# 2_ESP32.net
KiCad netlist of a schematic drawn in Altium Designer
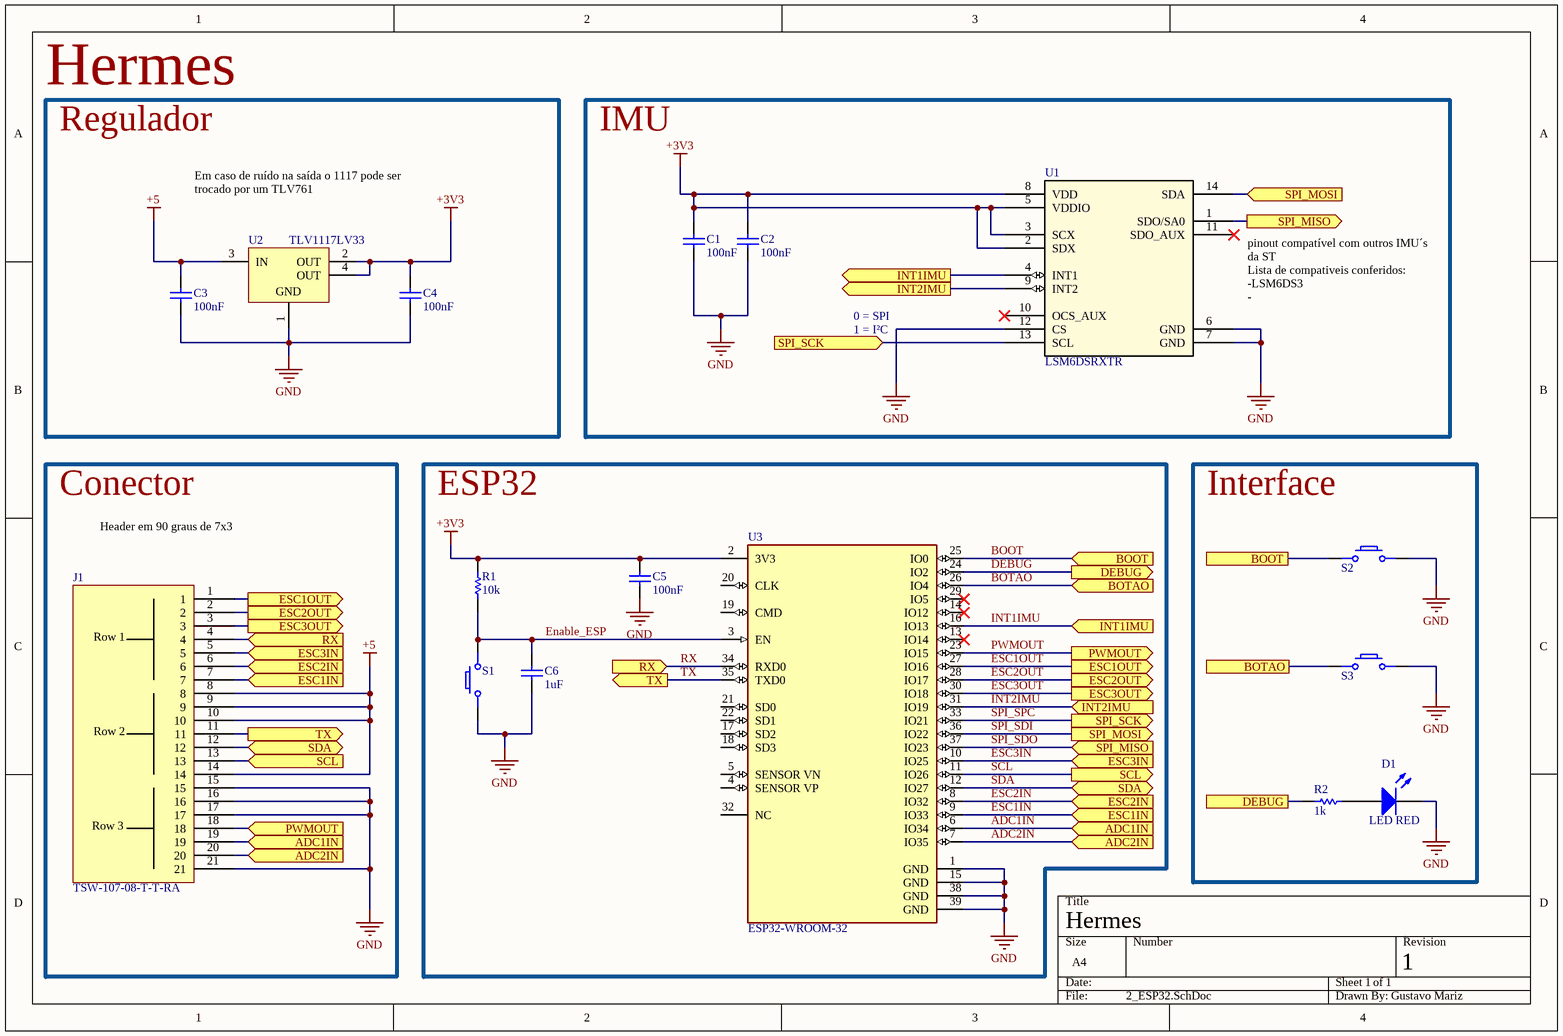
[diagram p0: 2_ESP32.SchDoc]

(export (version "E")
  (design (tool "Eeschema 10.0.6"))
  (components
    (comp (ref "C1")
      (value "CAP")
      (footprint "0603")
      (description "Capacitor")
      (fields (field (name "VALOR") "100nF"))
      (libsource (lib "Biblioteca Trincabotz (1)") (part "CAP. CERÂMICO"))
    )
    (comp (ref "C2")
      (value "CAP")
      (footprint "0603")
      (description "Capacitor")
      (fields (field (name "VALOR") "100nF"))
      (libsource (lib "Biblioteca Trincabotz (1)") (part "CAP. CERÂMICO"))
    )
    (comp (ref "C3")
      (value "CAP")
      (footprint "0603")
      (description "Capacitor")
      (fields (field (name "VALOR") "100nF"))
      (libsource (lib "Biblioteca Trincabotz (1)") (part "CAP. CERÂMICO"))
    )
    (comp (ref "C4")
      (value "CAP")
      (footprint "0603")
      (description "Capacitor")
      (fields (field (name "VALOR") "100nF"))
      (libsource (lib "Biblioteca Trincabotz (1)") (part "CAP. CERÂMICO"))
    )
    (comp (ref "C5")
      (value "CAP")
      (footprint "0603")
      (description "Capacitor")
      (fields (field (name "VALOR") "100nF"))
      (libsource (lib "Biblioteca Trincabotz (1)") (part "CAP. CERÂMICO"))
    )
    (comp (ref "C6")
      (value "CAP")
      (footprint "0603")
      (description "Capacitor")
      (fields (field (name "VALOR") "1uF"))
      (libsource (lib "Biblioteca Trincabotz (1)") (part "CAP. CERÂMICO"))
    )
    (comp (ref "D1")
      (value "LED RED")
      (footprint "LED 0805")
      (libsource (lib "Biblioteca Trincabotz (1)") (part "LED"))
    )
    (comp (ref "J1")
      (value "TSW-107-08-T-T-RA")
      (footprint "TSW-107-08-T-T-RA_SAI")
      (description "No Description Available")
      (libsource (lib "3x7pinheader") (part "TSW-107-08-T-T-RA"))
    )
    (comp (ref "R1")
      (value "10k")
      (footprint "RES 0603")
      (description "Resistor")
      (fields (field (name "Comment") "RESISTOR"))
      (libsource (lib "Biblioteca Trincabotz (1)") (part "RESISTOR"))
    )
    (comp (ref "R2")
      (value "1k")
      (footprint "RES 0603")
      (description "Resistor")
      (fields (field (name "Comment") "RESISTOR"))
      (libsource (lib "Biblioteca Trincabotz (1)") (part "RESISTOR"))
    )
    (comp (ref "S1")
      (value "PushButtonSMD")
      (footprint "PUSHBUTTON.SMD")
      (libsource (lib "Biblioteca Trincabotz (1)") (part "PushButtonSMD"))
    )
    (comp (ref "S2")
      (value "PushButtonSMD")
      (footprint "PUSHBUTTON.SMD")
      (libsource (lib "Biblioteca Trincabotz (1)") (part "PushButtonSMD"))
    )
    (comp (ref "S3")
      (value "PushButtonSMD")
      (footprint "PUSHBUTTON.SMD")
      (libsource (lib "Biblioteca Trincabotz (1)") (part "PushButtonSMD"))
    )
    (comp (ref "U1")
      (value "LSM6DSRXTR")
      (footprint "LGA-14L_STM")
      (description "No Description Available")
      (libsource (lib "LSM6DSRXTR") (part "LSM6DSRXTR"))
    )
    (comp (ref "U2")
      (value "TLV1117LV33")
      (footprint "DCY0004A_N")
      (fields (field (name "MANUFACTURER") "Texas Instruments") (field (name "PARTNUMBER") "TLV1117LV33DCYR"))
      (libsource (lib "Altium Content Vault") (part "TI-TLV1117LV33DCY4"))
    )
    (comp (ref "U3")
      (value "ESP32-WROOM-32")
      (footprint "FP-ESP32-WROOM-32-MFG")
      (description "RX TXRX MOD WIFI SURFACE MOUNT")
      (libsource (lib "Altium Content Vault") (part "ee866abf0b6c51247b7f5cdebf2f250"))
    )
  )
  (nets
    (net (code "1") (name "+3V3") (class "Default")
      (node (ref "C1") (pin "2") (pinfunction "2_2") (pintype "passive"))
      (node (ref "C2") (pin "2") (pinfunction "2_2") (pintype "passive"))
      (node (ref "C4") (pin "2") (pinfunction "2_2") (pintype "passive"))
      (node (ref "C5") (pin "2") (pinfunction "2_2") (pintype "passive"))
      (node (ref "R1") (pin "2") (pinfunction "2_2") (pintype "passive"))
      (node (ref "U1") (pin "2") (pinfunction "SDX_2") (pintype "passive"))
      (node (ref "U1") (pin "3") (pinfunction "SCX_3") (pintype "passive"))
      (node (ref "U1") (pin "5") (pinfunction "VDDIO_5") (pintype "power_in"))
      (node (ref "U1") (pin "8") (pinfunction "VDD_8") (pintype "power_in"))
      (node (ref "U2") (pin "2") (pinfunction "OUT_2") (pintype "power_in"))
      (node (ref "U2") (pin "4") (pinfunction "OUT_4") (pintype "power_in"))
      (node (ref "U3") (pin "2") (pinfunction "3V3_2") (pintype "power_in"))
    )
    (net (code "2") (name "+5") (class "Default")
      (node (ref "C3") (pin "2") (pinfunction "2_2") (pintype "passive"))
      (node (ref "J1") (pin "10") (pinfunction "10_10") (pintype "passive"))
      (node (ref "J1") (pin "14") (pinfunction "14_14") (pintype "passive"))
      (node (ref "J1") (pin "8") (pinfunction "8_8") (pintype "passive"))
      (node (ref "J1") (pin "9") (pinfunction "9_9") (pintype "passive"))
      (node (ref "U2") (pin "3") (pinfunction "IN_3") (pintype "power_in"))
    )
    (net (code "3") (name "/ADC1IN") (class "Default")
      (node (ref "J1") (pin "19") (pinfunction "19_19") (pintype "passive"))
      (node (ref "U3") (pin "6") (pinfunction "IO34_6") (pintype "bidirectional"))
    )
    (net (code "4") (name "/ADC2IN") (class "Default")
      (node (ref "J1") (pin "20") (pinfunction "20_20") (pintype "passive"))
      (node (ref "U3") (pin "7") (pinfunction "IO35_7") (pintype "bidirectional"))
    )
    (net (code "5") (name "/BOOT") (class "Default")
      (node (ref "S2") (pin "1") (pinfunction "1_1") (pintype "passive"))
      (node (ref "U3") (pin "25") (pinfunction "IO0_25") (pintype "bidirectional"))
    )
    (net (code "6") (name "/BOTAO") (class "Default")
      (node (ref "S3") (pin "1") (pinfunction "1_1") (pintype "passive"))
      (node (ref "U3") (pin "26") (pinfunction "IO4_26") (pintype "bidirectional"))
    )
    (net (code "7") (name "/DEBUG") (class "Default")
      (node (ref "R2") (pin "2") (pinfunction "2_2") (pintype "passive"))
      (node (ref "U3") (pin "24") (pinfunction "IO2_24") (pintype "bidirectional"))
    )
    (net (code "8") (name "/ESC1IN") (class "Default")
      (node (ref "J1") (pin "7") (pinfunction "7_7") (pintype "passive"))
      (node (ref "U3") (pin "9") (pinfunction "IO33_9") (pintype "bidirectional"))
    )
    (net (code "9") (name "/ESC1OUT") (class "Default")
      (node (ref "J1") (pin "1") (pinfunction "1_1") (pintype "passive"))
      (node (ref "U3") (pin "27") (pinfunction "IO16_27") (pintype "bidirectional"))
    )
    (net (code "10") (name "/ESC2IN") (class "Default")
      (node (ref "J1") (pin "6") (pinfunction "6_6") (pintype "passive"))
      (node (ref "U3") (pin "8") (pinfunction "IO32_8") (pintype "bidirectional"))
    )
    (net (code "11") (name "/ESC2OUT") (class "Default")
      (node (ref "J1") (pin "2") (pinfunction "2_2") (pintype "passive"))
      (node (ref "U3") (pin "28") (pinfunction "IO17_28") (pintype "bidirectional"))
    )
    (net (code "12") (name "/ESC3IN") (class "Default")
      (node (ref "J1") (pin "5") (pinfunction "5_5") (pintype "passive"))
      (node (ref "U3") (pin "10") (pinfunction "IO25_10") (pintype "bidirectional"))
    )
    (net (code "13") (name "/ESC3OUT") (class "Default")
      (node (ref "J1") (pin "3") (pinfunction "3_3") (pintype "passive"))
      (node (ref "U3") (pin "30") (pinfunction "IO18_30") (pintype "bidirectional"))
    )
    (net (code "14") (name "/Enable_ESP") (class "Default")
      (node (ref "C6") (pin "2") (pinfunction "2_2") (pintype "passive"))
      (node (ref "R1") (pin "1") (pinfunction "1_1") (pintype "passive"))
      (node (ref "S1") (pin "1") (pinfunction "1_1") (pintype "passive"))
      (node (ref "U3") (pin "3") (pinfunction "EN_3") (pintype "input"))
    )
    (net (code "15") (name "/INT1IMU") (class "Default")
      (node (ref "U1") (pin "4") (pinfunction "INT1_4") (pintype "bidirectional"))
      (node (ref "U3") (pin "16") (pinfunction "IO13_16") (pintype "bidirectional"))
    )
    (net (code "16") (name "/INT2IMU") (class "Default")
      (node (ref "U1") (pin "9") (pinfunction "INT2_9") (pintype "bidirectional"))
      (node (ref "U3") (pin "31") (pinfunction "IO19_31") (pintype "bidirectional"))
    )
    (net (code "17") (name "/PWMOUT") (class "Default")
      (node (ref "J1") (pin "18") (pinfunction "18_18") (pintype "passive"))
      (node (ref "U3") (pin "23") (pinfunction "IO15_23") (pintype "bidirectional"))
    )
    (net (code "18") (name "/RX") (class "Default")
      (node (ref "J1") (pin "4") (pinfunction "4_4") (pintype "passive"))
      (node (ref "U3") (pin "34") (pinfunction "RXD0_34") (pintype "bidirectional"))
    )
    (net (code "19") (name "/SCL") (class "Default")
      (node (ref "J1") (pin "13") (pinfunction "13_13") (pintype "passive"))
      (node (ref "U3") (pin "11") (pinfunction "IO26_11") (pintype "bidirectional"))
    )
    (net (code "20") (name "/SDA") (class "Default")
      (node (ref "J1") (pin "12") (pinfunction "12_12") (pintype "passive"))
      (node (ref "U3") (pin "12") (pinfunction "IO27_12") (pintype "bidirectional"))
    )
    (net (code "21") (name "/SPI_SDI") (class "Default")
      (node (ref "U1") (pin "14") (pinfunction "SDA_14") (pintype "passive"))
      (node (ref "U3") (pin "36") (pinfunction "IO22_36") (pintype "bidirectional"))
    )
    (net (code "22") (name "/SPI_SDO") (class "Default")
      (node (ref "U1") (pin "1") (pinfunction "SDO/SA0_1") (pintype "passive"))
      (node (ref "U3") (pin "37") (pinfunction "IO23_37") (pintype "bidirectional"))
    )
    (net (code "23") (name "/SPI_SPC") (class "Default")
      (node (ref "U1") (pin "13") (pinfunction "SCL_13") (pintype "passive"))
      (node (ref "U3") (pin "33") (pinfunction "IO21_33") (pintype "bidirectional"))
    )
    (net (code "24") (name "/TX") (class "Default")
      (node (ref "J1") (pin "11") (pinfunction "11_11") (pintype "passive"))
      (node (ref "U3") (pin "35") (pinfunction "TXD0_35") (pintype "bidirectional"))
    )
    (net (code "25") (name "GND") (class "Default")
      (node (ref "C1") (pin "1") (pinfunction "1_1") (pintype "passive"))
      (node (ref "C2") (pin "1") (pinfunction "1_1") (pintype "passive"))
      (node (ref "C3") (pin "1") (pinfunction "1_1") (pintype "passive"))
      (node (ref "C4") (pin "1") (pinfunction "1_1") (pintype "passive"))
      (node (ref "C5") (pin "1") (pinfunction "1_1") (pintype "passive"))
      (node (ref "C6") (pin "1") (pinfunction "1_1") (pintype "passive"))
      (node (ref "D1") (pin "2") (pinfunction "K_2") (pintype "passive"))
      (node (ref "J1") (pin "15") (pinfunction "15_15") (pintype "passive"))
      (node (ref "J1") (pin "16") (pinfunction "16_16") (pintype "passive"))
      (node (ref "J1") (pin "17") (pinfunction "17_17") (pintype "passive"))
      (node (ref "J1") (pin "21") (pinfunction "21_21") (pintype "passive"))
      (node (ref "S1") (pin "2") (pinfunction "2_2") (pintype "passive"))
      (node (ref "S2") (pin "2") (pinfunction "2_2") (pintype "passive"))
      (node (ref "S3") (pin "2") (pinfunction "2_2") (pintype "passive"))
      (node (ref "U1") (pin "12") (pinfunction "CS_12") (pintype "passive"))
      (node (ref "U1") (pin "6") (pinfunction "GND_6") (pintype "power_in"))
      (node (ref "U1") (pin "7") (pinfunction "GND_7") (pintype "power_in"))
      (node (ref "U2") (pin "1") (pinfunction "GND_1") (pintype "power_in"))
      (node (ref "U3") (pin "1") (pinfunction "GND_1") (pintype "power_in"))
      (node (ref "U3") (pin "15") (pinfunction "GND_15") (pintype "power_in"))
      (node (ref "U3") (pin "38") (pinfunction "GND_38") (pintype "power_in"))
      (node (ref "U3") (pin "39") (pinfunction "GND_39") (pintype "power_in"))
    )
    (net (code "26") (name "Net-(D1-A)") (class "Default")
      (node (ref "D1") (pin "1") (pinfunction "A_1") (pintype "passive"))
      (node (ref "R2") (pin "1") (pinfunction "1_1") (pintype "passive"))
    )
    (net (code "27") (name "unconnected-(U1-OCS_AUX-Pad10)") (class "Default")
      (node (ref "U1") (pin "10") (pinfunction "OCS_AUX_10") (pintype "passive+no_connect"))
    )
    (net (code "28") (name "unconnected-(U1-SDO_AUX-Pad11)") (class "Default")
      (node (ref "U1") (pin "11") (pinfunction "SDO_AUX_11") (pintype "passive+no_connect"))
    )
    (net (code "29") (name "unconnected-(U3-CLK-Pad20)") (class "Default")
      (node (ref "U3") (pin "20") (pinfunction "CLK_20") (pintype "bidirectional"))
    )
    (net (code "30") (name "unconnected-(U3-CMD-Pad19)") (class "Default")
      (node (ref "U3") (pin "19") (pinfunction "CMD_19") (pintype "bidirectional"))
    )
    (net (code "31") (name "unconnected-(U3-IO5-Pad29)") (class "Default")
      (node (ref "U3") (pin "29") (pinfunction "IO5_29") (pintype "bidirectional+no_connect"))
    )
    (net (code "32") (name "unconnected-(U3-IO12-Pad14)") (class "Default")
      (node (ref "U3") (pin "14") (pinfunction "IO12_14") (pintype "bidirectional+no_connect"))
    )
    (net (code "33") (name "unconnected-(U3-IO14-Pad13)") (class "Default")
      (node (ref "U3") (pin "13") (pinfunction "IO14_13") (pintype "bidirectional+no_connect"))
    )
    (net (code "34") (name "unconnected-(U3-NC-Pad32)") (class "Default")
      (node (ref "U3") (pin "32") (pinfunction "NC_32") (pintype "passive"))
    )
    (net (code "35") (name "unconnected-(U3-SD0-Pad21)") (class "Default")
      (node (ref "U3") (pin "21") (pinfunction "SD0_21") (pintype "bidirectional"))
    )
    (net (code "36") (name "unconnected-(U3-SD1-Pad22)") (class "Default")
      (node (ref "U3") (pin "22") (pinfunction "SD1_22") (pintype "bidirectional"))
    )
    (net (code "37") (name "unconnected-(U3-SD2-Pad17)") (class "Default")
      (node (ref "U3") (pin "17") (pinfunction "SD2_17") (pintype "bidirectional"))
    )
    (net (code "38") (name "unconnected-(U3-SD3-Pad18)") (class "Default")
      (node (ref "U3") (pin "18") (pinfunction "SD3_18") (pintype "bidirectional"))
    )
    (net (code "39") (name "unconnected-(U3-SENSOR_VN-Pad5)") (class "Default")
      (node (ref "U3") (pin "5") (pinfunction "SENSOR_VN_5") (pintype "bidirectional"))
    )
    (net (code "40") (name "unconnected-(U3-SENSOR_VP-Pad4)") (class "Default")
      (node (ref "U3") (pin "4") (pinfunction "SENSOR_VP_4") (pintype "bidirectional"))
    )
  )
)
